# 9_STM32F407_Controller.net
KiCad netlist of a schematic drawn in Altium Designer
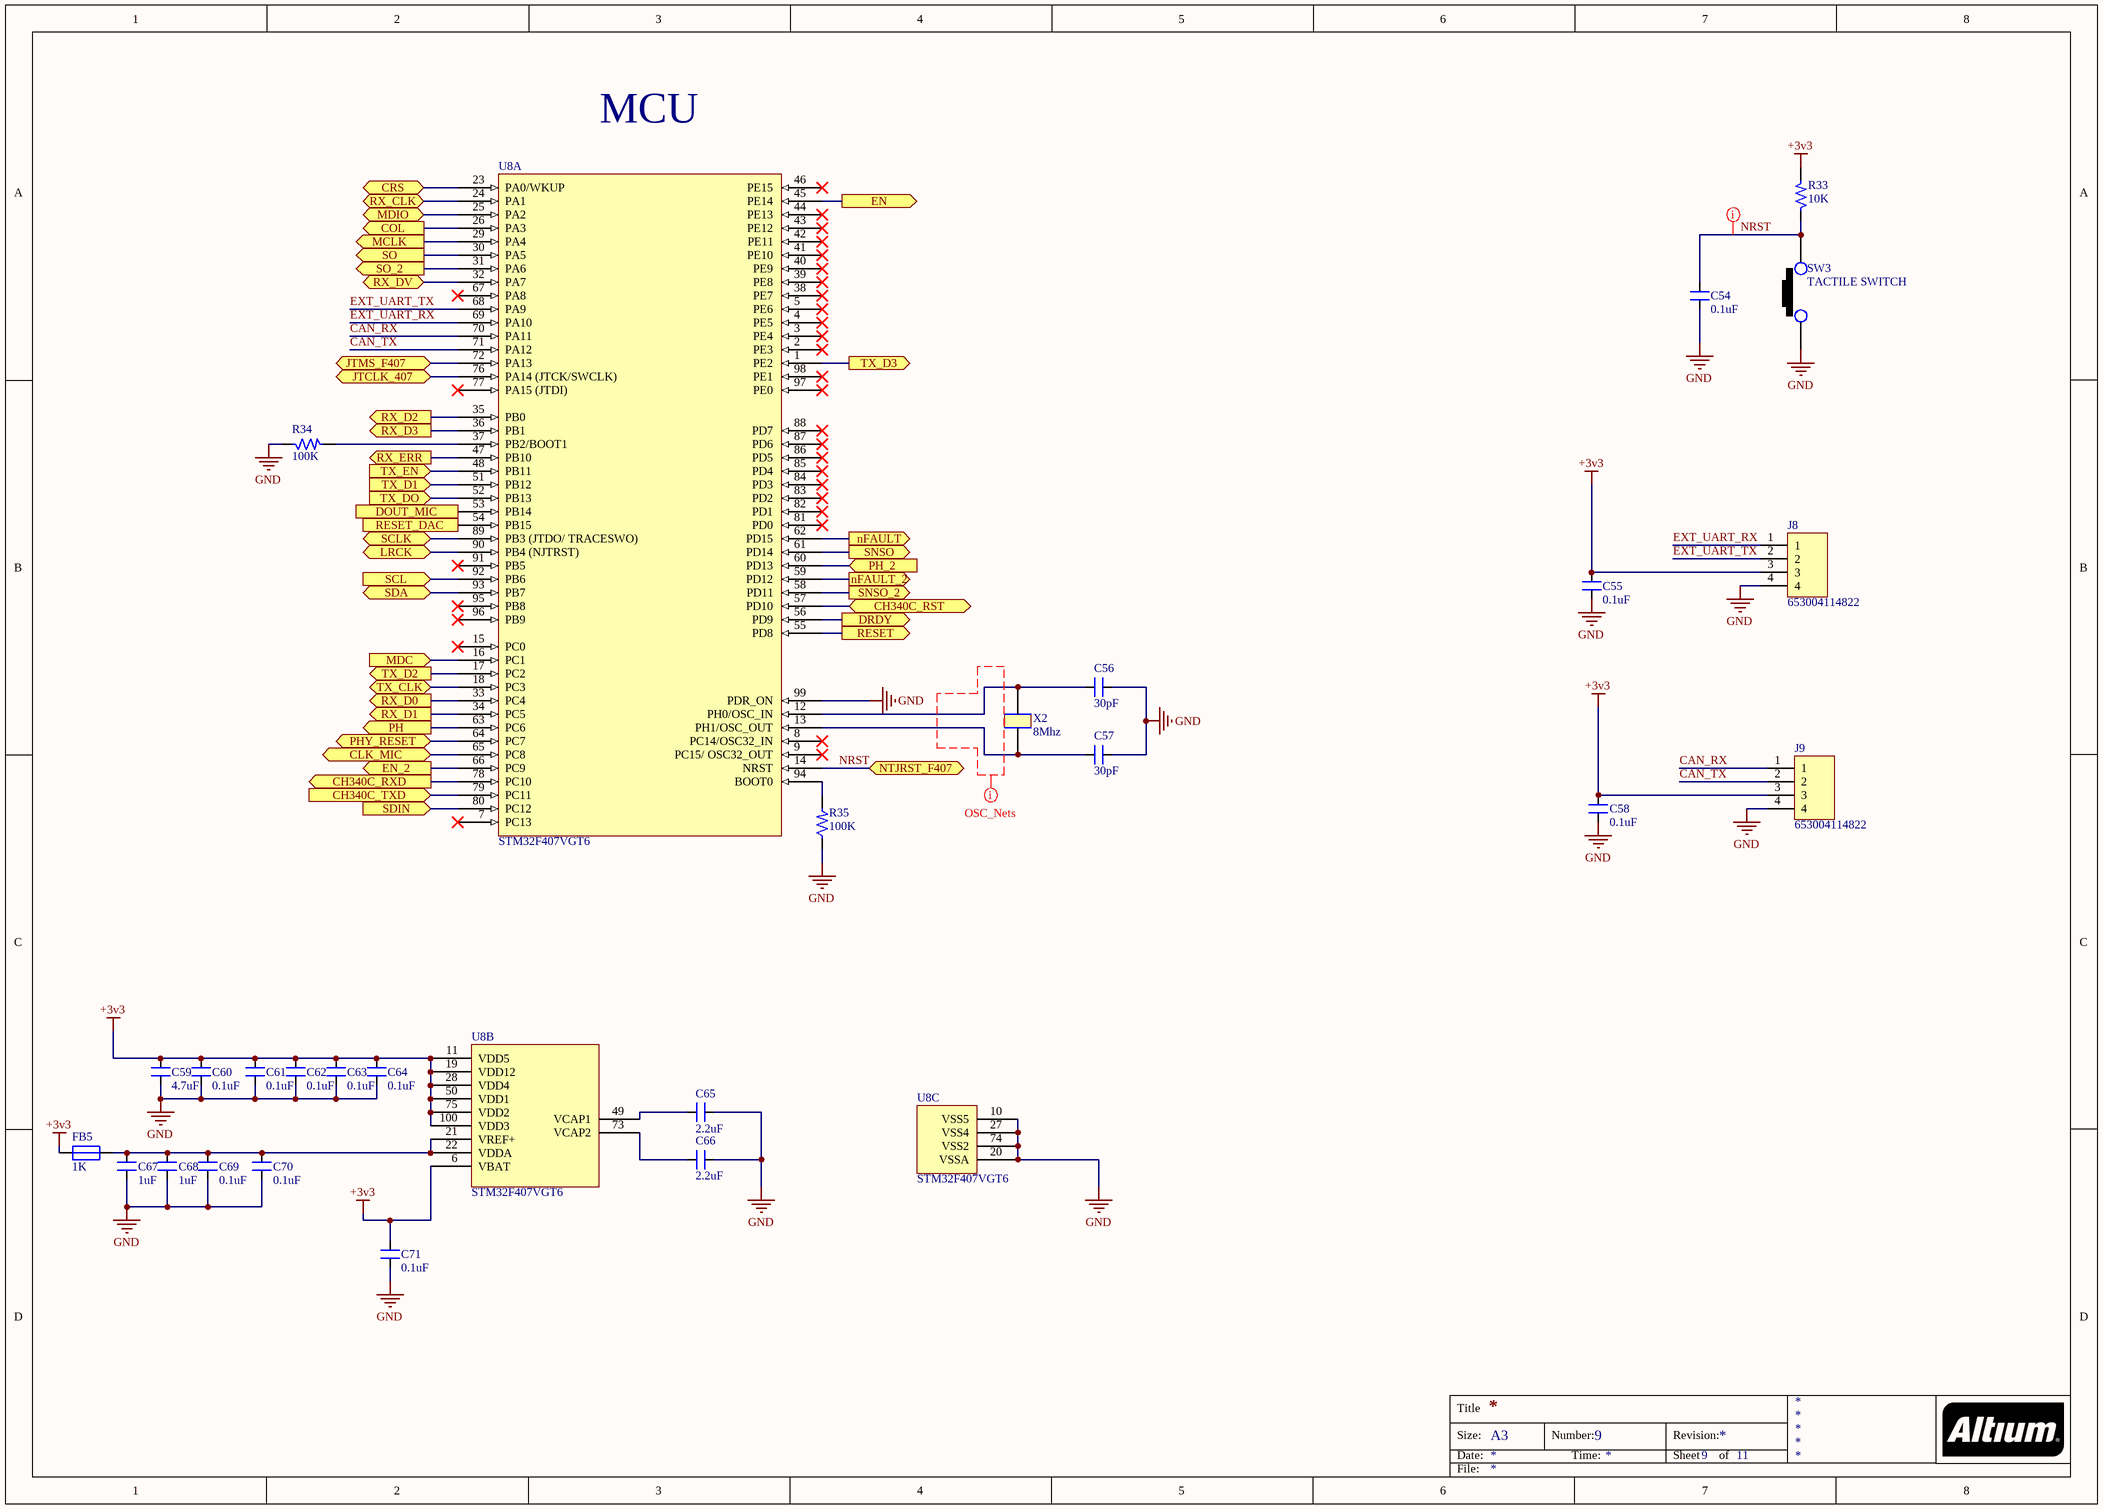
[diagram p0: [9]STM32F407_Controller.SchDoc]

(export (version "E")
  (design (tool "Eeschema 10.0.6"))
  (components
    (comp (ref "C54")
      (value "0.1uF")
      (footprint "CAP_0805")
      (description "0.1µF ±5% 50V Ceramic Capacitor X7R 0805 (2012 Metric)")
      (fields
        (field (name "MANUFACTURER") "AVX Corporation")
        (field (name "MANUFACTURER PART NUMBER") "08055C104JAT4A")
      )
      (libsource (lib "ESTEEMPCBLIB") (part "CAP_0.1uF-50V-5%-0805"))
    )
    (comp (ref "C55")
      (value "0.1uF")
      (footprint "CAP_0805")
      (description "0.1µF ±5% 50V Ceramic Capacitor X7R 0805 (2012 Metric)")
      (fields
        (field (name "MANUFACTURER") "AVX Corporation")
        (field (name "MANUFACTURER PART NUMBER") "08055C104JAT4A")
      )
      (libsource (lib "ESTEEMPCBLIB") (part "CAP_0.1uF-50V-5%-0805"))
    )
    (comp (ref "C56")
      (value "30pF")
      (footprint "CAP_0805")
      (description "±10% 50V Ceramic Capacitor C0G, NP0 0805 (2012 Metric)")
      (fields
        (field (name "MANUFACTURER PART NUMBER") "C0805C300K5GAC7800")
        (field (name "MANUFACTURER") "KEMET")
      )
      (libsource (lib "ESTEEMPCBLIB") (part "CAP_30pF-50V-10%-0805"))
    )
    (comp (ref "C57")
      (value "30pF")
      (footprint "CAP_0805")
      (description "±10% 50V Ceramic Capacitor C0G, NP0 0805 (2012 Metric)")
      (fields
        (field (name "MANUFACTURER PART NUMBER") "C0805C300K5GAC7800")
        (field (name "MANUFACTURER") "KEMET")
      )
      (libsource (lib "ESTEEMPCBLIB") (part "CAP_30pF-50V-10%-0805"))
    )
    (comp (ref "C58")
      (value "0.1uF")
      (footprint "CAP_0805")
      (description "0.1µF ±5% 50V Ceramic Capacitor X7R 0805 (2012 Metric)")
      (fields
        (field (name "MANUFACTURER") "AVX Corporation")
        (field (name "MANUFACTURER PART NUMBER") "08055C104JAT4A")
      )
      (libsource (lib "ESTEEMPCBLIB") (part "CAP_0.1uF-50V-5%-0805"))
    )
    (comp (ref "C59")
      (value "4.7uF")
      (footprint "CAP_0805")
      (description "1µF ±5% 50V Ceramic Capacitor X7R 0805 (2012 Metric)")
      (fields
        (field (name "MANUFACTURER") "Samsung")
        (field (name "MANUFACTURER PART NUMBER") "CC0805JKX7R9BB105")
      )
      (libsource (lib "ESTEEMPCBLIB") (part "CAP_1uF-50V-5%-0805"))
    )
    (comp (ref "C60")
      (value "0.1uF")
      (footprint "CAP_0805")
      (description "0.1µF ±5% 50V Ceramic Capacitor X7R 0805 (2012 Metric)")
      (fields
        (field (name "MANUFACTURER") "AVX Corporation")
        (field (name "MANUFACTURER PART NUMBER") "08055C104JAT4A")
      )
      (libsource (lib "ESTEEMPCBLIB") (part "CAP_0.1uF-50V-5%-0805"))
    )
    (comp (ref "C61")
      (value "0.1uF")
      (footprint "CAP_0805")
      (description "0.1µF ±5% 50V Ceramic Capacitor X7R 0805 (2012 Metric)")
      (fields
        (field (name "MANUFACTURER") "AVX Corporation")
        (field (name "MANUFACTURER PART NUMBER") "08055C104JAT4A")
      )
      (libsource (lib "ESTEEMPCBLIB") (part "CAP_0.1uF-50V-5%-0805"))
    )
    (comp (ref "C62")
      (value "0.1uF")
      (footprint "CAP_0805")
      (description "0.1µF ±5% 50V Ceramic Capacitor X7R 0805 (2012 Metric)")
      (fields
        (field (name "MANUFACTURER") "AVX Corporation")
        (field (name "MANUFACTURER PART NUMBER") "08055C104JAT4A")
      )
      (libsource (lib "ESTEEMPCBLIB") (part "CAP_0.1uF-50V-5%-0805"))
    )
    (comp (ref "C63")
      (value "0.1uF")
      (footprint "CAP_0805")
      (description "0.1µF ±5% 50V Ceramic Capacitor X7R 0805 (2012 Metric)")
      (fields
        (field (name "MANUFACTURER") "AVX Corporation")
        (field (name "MANUFACTURER PART NUMBER") "08055C104JAT4A")
      )
      (libsource (lib "ESTEEMPCBLIB") (part "CAP_0.1uF-50V-5%-0805"))
    )
    (comp (ref "C64")
      (value "0.1uF")
      (footprint "CAP_0805")
      (description "0.1µF ±5% 50V Ceramic Capacitor X7R 0805 (2012 Metric)")
      (fields
        (field (name "MANUFACTURER") "AVX Corporation")
        (field (name "MANUFACTURER PART NUMBER") "08055C104JAT4A")
      )
      (libsource (lib "ESTEEMPCBLIB") (part "CAP_0.1uF-50V-5%-0805"))
    )
    (comp (ref "C65")
      (value "2.2uF")
      (footprint "CAP_0805")
      (description "2.2µF ±10% 25V Ceramic Capacitor X7R 0805 (2012 Metric)")
      (fields
        (field (name "MANUFACTURER") "KEMET")
        (field (name "MANUFACTURER PART NUMBER") "CL21B225KAFNFNE")
      )
      (libsource (lib "ESTEEMPCBLIB") (part "CAP_2.2uF-25V-10%-0805"))
    )
    (comp (ref "C66")
      (value "2.2uF")
      (footprint "CAP_0805")
      (description "2.2µF ±10% 25V Ceramic Capacitor X7R 0805 (2012 Metric)")
      (fields
        (field (name "MANUFACTURER") "KEMET")
        (field (name "MANUFACTURER PART NUMBER") "CL21B225KAFNFNE")
      )
      (libsource (lib "ESTEEMPCBLIB") (part "CAP_2.2uF-25V-10%-0805"))
    )
    (comp (ref "C67")
      (value "1uF")
      (footprint "CAP_0805")
      (description "1µF ±5% 50V Ceramic Capacitor X7R 0805 (2012 Metric)")
      (fields
        (field (name "MANUFACTURER") "Samsung")
        (field (name "MANUFACTURER PART NUMBER") "CC0805JKX7R9BB105")
      )
      (libsource (lib "ESTEEMPCBLIB") (part "CAP_1uF-50V-5%-0805"))
    )
    (comp (ref "C68")
      (value "1uF")
      (footprint "CAP_0805")
      (description "1µF ±5% 50V Ceramic Capacitor X7R 0805 (2012 Metric)")
      (fields
        (field (name "MANUFACTURER") "Samsung")
        (field (name "MANUFACTURER PART NUMBER") "CC0805JKX7R9BB105")
      )
      (libsource (lib "ESTEEMPCBLIB") (part "CAP_1uF-50V-5%-0805"))
    )
    (comp (ref "C69")
      (value "0.1uF")
      (footprint "CAP_0805")
      (description "0.1µF ±5% 50V Ceramic Capacitor X7R 0805 (2012 Metric)")
      (fields
        (field (name "MANUFACTURER") "AVX Corporation")
        (field (name "MANUFACTURER PART NUMBER") "08055C104JAT4A")
      )
      (libsource (lib "ESTEEMPCBLIB") (part "CAP_0.1uF-50V-5%-0805"))
    )
    (comp (ref "C70")
      (value "0.1uF")
      (footprint "CAP_0805")
      (description "0.1µF ±5% 50V Ceramic Capacitor X7R 0805 (2012 Metric)")
      (fields
        (field (name "MANUFACTURER") "AVX Corporation")
        (field (name "MANUFACTURER PART NUMBER") "08055C104JAT4A")
      )
      (libsource (lib "ESTEEMPCBLIB") (part "CAP_0.1uF-50V-5%-0805"))
    )
    (comp (ref "C71")
      (value "0.1uF")
      (footprint "CAP_0805")
      (description "0.1µF ±5% 50V Ceramic Capacitor X7R 0805 (2012 Metric)")
      (fields
        (field (name "MANUFACTURER") "AVX Corporation")
        (field (name "MANUFACTURER PART NUMBER") "08055C104JAT4A")
      )
      (libsource (lib "ESTEEMPCBLIB") (part "CAP_0.1uF-50V-5%-0805"))
    )
    (comp (ref "FB5")
      (value "1K")
      (footprint "IND_0805")
      (description "1 kOhms @ 100MHz 1 Power Line Ferrite Bead 0805 (2012 Metric) 1.6A")
      (fields
        (field (name "MANUFACTURER") "Laird")
        (field (name "MANUFACTURER PART NUMBER") "BLM21SP102SH1D")
      )
      (libsource (lib "ESTEEMPCBLIB") (part "FB_1K-100MHZ-1.6A-0805"))
    )
    (comp (ref "J8")
      (value "653004114822")
      (footprint "CON4_50_653004114822_TH_ST")
      (description "4 Pins, 1 Row 1.25mm Pitch, straight Connector, male")
      (fields (field (name "MANUFACTURER") "JST") (field (name "MATING PART NUMBER") "653004113322"))
      (libsource (lib "ESTEEMPCBLIB") (part "CON-PLG_4X1-50-ST-TH"))
    )
    (comp (ref "J9")
      (value "653004114822")
      (footprint "CON4_50_653004114822_TH_ST")
      (description "4 Pins, 1 Row 1.25mm Pitch, straight Connector, male")
      (fields (field (name "MANUFACTURER") "JST") (field (name "MATING PART NUMBER") "653004113322"))
      (libsource (lib "ESTEEMPCBLIB") (part "CON-PLG_4X1-50-ST-TH"))
    )
    (comp (ref "R33")
      (value "10K")
      (footprint "RES_0805")
      (description "10 kOhms ±1% 0.125W, 1/8W Chip Resistor 0805 (2012 Metric) Automotive AEC-Q200 Thick Film")
      (fields (field (name "MANUFACTURER") "CTS") (field (name "MANUFACTURER PART NUMBER") "WR08X1002FTL"))
      (libsource (lib "ESTEEMPCBLIB") (part "RES_10K-0.125W-1%-0805"))
    )
    (comp (ref "R34")
      (value "100K")
      (footprint "RES_0805")
      (description "100 kOhms ±1% 0.125W, 1/8W Chip Resistor 0805 (2012 Metric) Automotive AEC-Q200 Thick Film")
      (fields (field (name "MANUFACTURER") "Walsin") (field (name "MANUFACTURER PART NUMBER") "WR08X1003FTL"))
      (libsource (lib "ESTEEMPCBLIB") (part "RES_100K-0.125W-1%-0805"))
    )
    (comp (ref "R35")
      (value "100K")
      (footprint "RES_0805")
      (description "100 kOhms ±1% 0.125W, 1/8W Chip Resistor 0805 (2012 Metric) Automotive AEC-Q200 Thick Film")
      (fields (field (name "MANUFACTURER") "Walsin") (field (name "MANUFACTURER PART NUMBER") "WR08X1003FTL"))
      (libsource (lib "ESTEEMPCBLIB") (part "RES_100K-0.125W-1%-0805"))
    )
    (comp (ref "SW3")
      (value "TACTILE SWITCH")
      (footprint "SW_342_SMD")
      (description "Tactile Switch SPST-NO Top Actuated Surface Mount")
      (fields
        (field (name "MANUFACTURER") "ITT C&K")
        (field (name "MANUFACTURER PART NUMBER") "RS-282G05A3-SMRT")
      )
      (libsource (lib "ESTEEMPCBLIB") (part "SW1_RS-282G05A3-SMRT-SMD"))
    )
    (comp (ref "U8")
      (value "STM32F407VGT6")
      (footprint "QFN100_19.6_669_58X10_SMD")
      (description "ARM® Cortex®-M4 STM32F4 Microcontroller IC 32-Bit 168MHz 1MB (1M x 8) FLASH 100-LQFP (14x14)")
      (fields (field (name "MANUFACTURER") "STMicroelectronics"))
      (libsource (lib "ESTEEMPCBLIB") (part "IC_STM32F407VGT6"))
    )
    (comp (ref "X2")
      (value "8Mhz")
      (footprint "XTAL_314_240X47_SMD")
      (description "8MHz ±30ppm Crystal 32pF 60 Ohms HC-49/US")
      (fields
        (field (name "MANUFACTURER") "Fox Electronics")
        (field (name "MANUFACTURER PART NUMBER") "ECS-80-32-5PX-TR")
      )
      (libsource (lib "ESTEEMPCBLIB") (part "XTAL_8MHZ-ECS-80-32-5PX-SMD"))
    )
  )
  (nets
    (net (code "1") (name "+3v3") (class "Default")
      (node (ref "C55") (pin "2") (pinfunction "2_2") (pintype "passive"))
      (node (ref "C58") (pin "2") (pinfunction "2_2") (pintype "passive"))
      (node (ref "C59") (pin "2") (pinfunction "2_2") (pintype "passive"))
      (node (ref "C60") (pin "2") (pinfunction "2_2") (pintype "passive"))
      (node (ref "C61") (pin "2") (pinfunction "2_2") (pintype "passive"))
      (node (ref "C62") (pin "2") (pinfunction "2_2") (pintype "passive"))
      (node (ref "C63") (pin "2") (pinfunction "2_2") (pintype "passive"))
      (node (ref "C64") (pin "2") (pinfunction "2_2") (pintype "passive"))
      (node (ref "C71") (pin "2") (pinfunction "2_2") (pintype "passive"))
      (node (ref "FB5") (pin "1") (pinfunction "1_1") (pintype "passive"))
      (node (ref "J8") (pin "3") (pinfunction "3_3") (pintype "passive"))
      (node (ref "J9") (pin "3") (pinfunction "3_3") (pintype "passive"))
      (node (ref "R33") (pin "2") (pinfunction "2_2") (pintype "passive"))
      (node (ref "U8") (pin "100") (pinfunction "VDD3_100") (pintype "passive"))
      (node (ref "U8") (pin "11") (pinfunction "VDD5_11") (pintype "passive"))
      (node (ref "U8") (pin "19") (pinfunction "VDD12_19") (pintype "passive"))
      (node (ref "U8") (pin "28") (pinfunction "VDD4_28") (pintype "passive"))
      (node (ref "U8") (pin "50") (pinfunction "VDD1_50") (pintype "passive"))
      (node (ref "U8") (pin "6") (pinfunction "VBAT_6") (pintype "passive"))
      (node (ref "U8") (pin "75") (pinfunction "VDD2_75") (pintype "passive"))
    )
    (net (code "2") (name "/CAN_RX") (class "Default")
      (node (ref "J9") (pin "1") (pinfunction "1_1") (pintype "passive"))
      (node (ref "U8") (pin "70") (pinfunction "PA11_70") (pintype "input"))
    )
    (net (code "3") (name "/CAN_TX") (class "Default")
      (node (ref "J9") (pin "2") (pinfunction "2_2") (pintype "passive"))
      (node (ref "U8") (pin "71") (pinfunction "PA12_71") (pintype "input"))
    )
    (net (code "4") (name "/CH340C_RST") (class "Default")
      (node (ref "U8") (pin "57") (pinfunction "PD10_57") (pintype "input"))
    )
    (net (code "5") (name "/CH340C_RXD") (class "Default")
      (node (ref "U8") (pin "78") (pinfunction "PC10_78") (pintype "input"))
    )
    (net (code "6") (name "/CH340C_TXD") (class "Default")
      (node (ref "U8") (pin "79") (pinfunction "PC11_79") (pintype "input"))
    )
    (net (code "7") (name "/CLK_MIC") (class "Default")
      (node (ref "U8") (pin "65") (pinfunction "PC8_65") (pintype "input"))
    )
    (net (code "8") (name "/COL") (class "Default")
      (node (ref "U8") (pin "26") (pinfunction "PA3_26") (pintype "input"))
    )
    (net (code "9") (name "/CRS") (class "Default")
      (node (ref "U8") (pin "23") (pinfunction "PA0/WKUP_23") (pintype "input"))
    )
    (net (code "10") (name "/DOUT_MIC") (class "Default")
      (node (ref "U8") (pin "53") (pinfunction "PB14_53") (pintype "input"))
    )
    (net (code "11") (name "/DRDY") (class "Default")
      (node (ref "U8") (pin "56") (pinfunction "PD9_56") (pintype "input"))
    )
    (net (code "12") (name "/EN") (class "Default")
      (node (ref "U8") (pin "45") (pinfunction "PE14_45") (pintype "input"))
    )
    (net (code "13") (name "/EN_2") (class "Default")
      (node (ref "U8") (pin "66") (pinfunction "PC9_66") (pintype "input"))
    )
    (net (code "14") (name "/EXT_UART_RX") (class "Default")
      (node (ref "J8") (pin "1") (pinfunction "1_1") (pintype "passive"))
      (node (ref "U8") (pin "69") (pinfunction "PA10_69") (pintype "input"))
    )
    (net (code "15") (name "/EXT_UART_TX") (class "Default")
      (node (ref "J8") (pin "2") (pinfunction "2_2") (pintype "passive"))
      (node (ref "U8") (pin "68") (pinfunction "PA9_68") (pintype "input"))
    )
    (net (code "16") (name "/JTCLK_407") (class "Default")
      (node (ref "U8") (pin "76") (pinfunction "PA14_(JTCK/SWCLK)_76") (pintype "input"))
    )
    (net (code "17") (name "/JTMS_F407") (class "Default")
      (node (ref "U8") (pin "72") (pinfunction "PA13_72") (pintype "input"))
    )
    (net (code "18") (name "/LRCK") (class "Default")
      (node (ref "U8") (pin "90") (pinfunction "PB4_(NJTRST)_90") (pintype "input"))
    )
    (net (code "19") (name "/MCLK") (class "Default")
      (node (ref "U8") (pin "29") (pinfunction "PA4_29") (pintype "input"))
    )
    (net (code "20") (name "/MDC") (class "Default")
      (node (ref "U8") (pin "16") (pinfunction "PC1_16") (pintype "input"))
    )
    (net (code "21") (name "/MDIO") (class "Default")
      (node (ref "U8") (pin "25") (pinfunction "PA2_25") (pintype "input"))
    )
    (net (code "22") (name "/NRST") (class "Default")
      (node (ref "C54") (pin "2") (pinfunction "2_2") (pintype "passive"))
      (node (ref "R33") (pin "1") (pinfunction "1_1") (pintype "passive"))
      (node (ref "SW3") (pin "2") (pinfunction "2_2") (pintype "passive"))
      (node (ref "U8") (pin "14") (pinfunction "NRST_14") (pintype "input"))
    )
    (net (code "23") (name "/PH") (class "Default")
      (node (ref "U8") (pin "63") (pinfunction "PC6_63") (pintype "input"))
    )
    (net (code "24") (name "/PHY_RESET") (class "Default")
      (node (ref "U8") (pin "64") (pinfunction "PC7_64") (pintype "input"))
    )
    (net (code "25") (name "/PH_2") (class "Default")
      (node (ref "U8") (pin "60") (pinfunction "PD13_60") (pintype "input"))
    )
    (net (code "26") (name "/RESET") (class "Default")
      (node (ref "U8") (pin "55") (pinfunction "PD8_55") (pintype "input"))
    )
    (net (code "27") (name "/RESET_DAC") (class "Default")
      (node (ref "U8") (pin "54") (pinfunction "PB15_54") (pintype "input"))
    )
    (net (code "28") (name "/RX_CLK") (class "Default")
      (node (ref "U8") (pin "24") (pinfunction "PA1_24") (pintype "input"))
    )
    (net (code "29") (name "/RX_D0") (class "Default")
      (node (ref "U8") (pin "33") (pinfunction "PC4_33") (pintype "input"))
    )
    (net (code "30") (name "/RX_D1") (class "Default")
      (node (ref "U8") (pin "34") (pinfunction "PC5_34") (pintype "input"))
    )
    (net (code "31") (name "/RX_D2") (class "Default")
      (node (ref "U8") (pin "35") (pinfunction "PB0_35") (pintype "input"))
    )
    (net (code "32") (name "/RX_D3") (class "Default")
      (node (ref "U8") (pin "36") (pinfunction "PB1_36") (pintype "input"))
    )
    (net (code "33") (name "/RX_DV") (class "Default")
      (node (ref "U8") (pin "32") (pinfunction "PA7_32") (pintype "input"))
    )
    (net (code "34") (name "/RX_ERR") (class "Default")
      (node (ref "U8") (pin "47") (pinfunction "PB10_47") (pintype "input"))
    )
    (net (code "35") (name "/SCL") (class "Default")
      (node (ref "U8") (pin "92") (pinfunction "PB6_92") (pintype "input"))
    )
    (net (code "36") (name "/SCLK") (class "Default")
      (node (ref "U8") (pin "89") (pinfunction "PB3_(JTDO/_TRACESWO)_89") (pintype "input"))
    )
    (net (code "37") (name "/SDA") (class "Default")
      (node (ref "U8") (pin "93") (pinfunction "PB7_93") (pintype "input"))
    )
    (net (code "38") (name "/SDIN") (class "Default")
      (node (ref "U8") (pin "80") (pinfunction "PC12_80") (pintype "input"))
    )
    (net (code "39") (name "/SNSO") (class "Default")
      (node (ref "U8") (pin "61") (pinfunction "PD14_61") (pintype "input"))
    )
    (net (code "40") (name "/SNSO_2") (class "Default")
      (node (ref "U8") (pin "58") (pinfunction "PD11_58") (pintype "input"))
    )
    (net (code "41") (name "/SO") (class "Default")
      (node (ref "U8") (pin "30") (pinfunction "PA5_30") (pintype "input"))
    )
    (net (code "42") (name "/SO_2") (class "Default")
      (node (ref "U8") (pin "31") (pinfunction "PA6_31") (pintype "input"))
    )
    (net (code "43") (name "/TX_CLK") (class "Default")
      (node (ref "U8") (pin "18") (pinfunction "PC3_18") (pintype "input"))
    )
    (net (code "44") (name "/TX_D1") (class "Default")
      (node (ref "U8") (pin "51") (pinfunction "PB12_51") (pintype "input"))
    )
    (net (code "45") (name "/TX_D2") (class "Default")
      (node (ref "U8") (pin "17") (pinfunction "PC2_17") (pintype "input"))
    )
    (net (code "46") (name "/TX_D3") (class "Default")
      (node (ref "U8") (pin "1") (pinfunction "PE2_1") (pintype "input"))
    )
    (net (code "47") (name "/TX_DO") (class "Default")
      (node (ref "U8") (pin "52") (pinfunction "PB13_52") (pintype "input"))
    )
    (net (code "48") (name "/TX_EN") (class "Default")
      (node (ref "U8") (pin "48") (pinfunction "PB11_48") (pintype "input"))
    )
    (net (code "49") (name "/nFAULT") (class "Default")
      (node (ref "U8") (pin "62") (pinfunction "PD15_62") (pintype "input"))
    )
    (net (code "50") (name "/nFAULT_2") (class "Default")
      (node (ref "U8") (pin "59") (pinfunction "PD12_59") (pintype "input"))
    )
    (net (code "51") (name "GND") (class "Default")
      (node (ref "C54") (pin "1") (pinfunction "1_1") (pintype "passive"))
      (node (ref "C55") (pin "1") (pinfunction "1_1") (pintype "passive"))
      (node (ref "C56") (pin "2") (pinfunction "2_2") (pintype "passive"))
      (node (ref "C57") (pin "2") (pinfunction "2_2") (pintype "passive"))
      (node (ref "C58") (pin "1") (pinfunction "1_1") (pintype "passive"))
      (node (ref "C59") (pin "1") (pinfunction "1_1") (pintype "passive"))
      (node (ref "C60") (pin "1") (pinfunction "1_1") (pintype "passive"))
      (node (ref "C61") (pin "1") (pinfunction "1_1") (pintype "passive"))
      (node (ref "C62") (pin "1") (pinfunction "1_1") (pintype "passive"))
      (node (ref "C63") (pin "1") (pinfunction "1_1") (pintype "passive"))
      (node (ref "C64") (pin "1") (pinfunction "1_1") (pintype "passive"))
      (node (ref "C65") (pin "2") (pinfunction "2_2") (pintype "passive"))
      (node (ref "C66") (pin "2") (pinfunction "2_2") (pintype "passive"))
      (node (ref "C67") (pin "1") (pinfunction "1_1") (pintype "passive"))
      (node (ref "C68") (pin "1") (pinfunction "1_1") (pintype "passive"))
      (node (ref "C69") (pin "1") (pinfunction "1_1") (pintype "passive"))
      (node (ref "C70") (pin "1") (pinfunction "1_1") (pintype "passive"))
      (node (ref "C71") (pin "1") (pinfunction "1_1") (pintype "passive"))
      (node (ref "J8") (pin "4") (pinfunction "4_4") (pintype "passive"))
      (node (ref "J9") (pin "4") (pinfunction "4_4") (pintype "passive"))
      (node (ref "R34") (pin "1") (pinfunction "1_1") (pintype "passive"))
      (node (ref "R35") (pin "1") (pinfunction "1_1") (pintype "passive"))
      (node (ref "SW3") (pin "1") (pinfunction "1_1") (pintype "passive"))
      (node (ref "U8") (pin "10") (pinfunction "VSS5_10") (pintype "passive"))
      (node (ref "U8") (pin "20") (pinfunction "VSSA_20") (pintype "passive"))
      (node (ref "U8") (pin "27") (pinfunction "VSS4_27") (pintype "passive"))
      (node (ref "U8") (pin "74") (pinfunction "VSS2_74") (pintype "passive"))
      (node (ref "U8") (pin "99") (pinfunction "PDR_ON_99") (pintype "input"))
    )
    (net (code "52") (name "Net-(U8A-BOOT0)") (class "Default")
      (node (ref "R35") (pin "2") (pinfunction "2_2") (pintype "passive"))
      (node (ref "U8") (pin "94") (pinfunction "BOOT0_94") (pintype "input"))
    )
    (net (code "53") (name "Net-(U8A-PB2{slash}BOOT1)") (class "Default")
      (node (ref "R34") (pin "2") (pinfunction "2_2") (pintype "passive"))
      (node (ref "U8") (pin "37") (pinfunction "PB2/BOOT1_37") (pintype "input"))
    )
    (net (code "54") (name "Net-(U8A-PH0{slash}OSC_IN)") (class "Default")
      (node (ref "C56") (pin "1") (pinfunction "1_1") (pintype "passive"))
      (node (ref "U8") (pin "12") (pinfunction "PH0/OSC_IN_12") (pintype "input"))
      (node (ref "X2") (pin "2") (pinfunction "2_2") (pintype "passive"))
    )
    (net (code "55") (name "Net-(U8A-PH1{slash}OSC_OUT)") (class "Default")
      (node (ref "C57") (pin "1") (pinfunction "1_1") (pintype "passive"))
      (node (ref "U8") (pin "13") (pinfunction "PH1/OSC_OUT_13") (pintype "input"))
      (node (ref "X2") (pin "1") (pinfunction "1_1") (pintype "passive"))
    )
    (net (code "56") (name "Net-(U8B-VCAP1)") (class "Default")
      (node (ref "C65") (pin "1") (pinfunction "1_1") (pintype "passive"))
      (node (ref "U8") (pin "49") (pinfunction "VCAP1_49") (pintype "passive"))
    )
    (net (code "57") (name "Net-(U8B-VCAP2)") (class "Default")
      (node (ref "C66") (pin "1") (pinfunction "1_1") (pintype "passive"))
      (node (ref "U8") (pin "73") (pinfunction "VCAP2_73") (pintype "passive"))
    )
    (net (code "58") (name "Net-(U8B-VDDA)") (class "Default")
      (node (ref "C67") (pin "2") (pinfunction "2_2") (pintype "passive"))
      (node (ref "C68") (pin "2") (pinfunction "2_2") (pintype "passive"))
      (node (ref "C69") (pin "2") (pinfunction "2_2") (pintype "passive"))
      (node (ref "C70") (pin "2") (pinfunction "2_2") (pintype "passive"))
      (node (ref "FB5") (pin "2") (pinfunction "2_2") (pintype "passive"))
      (node (ref "U8") (pin "21") (pinfunction "VREF+_21") (pintype "passive"))
      (node (ref "U8") (pin "22") (pinfunction "VDDA_22") (pintype "passive"))
    )
    (net (code "59") (name "unconnected-(U8A-PA8-Pad67)") (class "Default")
      (node (ref "U8") (pin "67") (pinfunction "PA8_67") (pintype "input+no_connect"))
    )
    (net (code "60") (name "unconnected-(U8A-PA15_(JTDI)-Pad77)") (class "Default")
      (node (ref "U8") (pin "77") (pinfunction "PA15_(JTDI)_77") (pintype "input+no_connect"))
    )
    (net (code "61") (name "unconnected-(U8A-PB5-Pad91)") (class "Default")
      (node (ref "U8") (pin "91") (pinfunction "PB5_91") (pintype "input+no_connect"))
    )
    (net (code "62") (name "unconnected-(U8A-PB8-Pad95)") (class "Default")
      (node (ref "U8") (pin "95") (pinfunction "PB8_95") (pintype "input+no_connect"))
    )
    (net (code "63") (name "unconnected-(U8A-PB9-Pad96)") (class "Default")
      (node (ref "U8") (pin "96") (pinfunction "PB9_96") (pintype "input+no_connect"))
    )
    (net (code "64") (name "unconnected-(U8A-PC0-Pad15)") (class "Default")
      (node (ref "U8") (pin "15") (pinfunction "PC0_15") (pintype "input+no_connect"))
    )
    (net (code "65") (name "unconnected-(U8A-PC13-Pad7)") (class "Default")
      (node (ref "U8") (pin "7") (pinfunction "PC13_7") (pintype "input+no_connect"))
    )
    (net (code "66") (name "unconnected-(U8A-PC14{slash}OSC32_IN-Pad8)") (class "Default")
      (node (ref "U8") (pin "8") (pinfunction "PC14/OSC32_IN_8") (pintype "input+no_connect"))
    )
    (net (code "67") (name "unconnected-(U8A-PC15{slash}_OSC32_OUT-Pad9)") (class "Default")
      (node (ref "U8") (pin "9") (pinfunction "PC15/_OSC32_OUT_9") (pintype "input+no_connect"))
    )
    (net (code "68") (name "unconnected-(U8A-PD0-Pad81)") (class "Default")
      (node (ref "U8") (pin "81") (pinfunction "PD0_81") (pintype "input+no_connect"))
    )
    (net (code "69") (name "unconnected-(U8A-PD1-Pad82)") (class "Default")
      (node (ref "U8") (pin "82") (pinfunction "PD1_82") (pintype "input+no_connect"))
    )
    (net (code "70") (name "unconnected-(U8A-PD2-Pad83)") (class "Default")
      (node (ref "U8") (pin "83") (pinfunction "PD2_83") (pintype "input+no_connect"))
    )
    (net (code "71") (name "unconnected-(U8A-PD3-Pad84)") (class "Default")
      (node (ref "U8") (pin "84") (pinfunction "PD3_84") (pintype "input+no_connect"))
    )
    (net (code "72") (name "unconnected-(U8A-PD4-Pad85)") (class "Default")
      (node (ref "U8") (pin "85") (pinfunction "PD4_85") (pintype "input+no_connect"))
    )
    (net (code "73") (name "unconnected-(U8A-PD5-Pad86)") (class "Default")
      (node (ref "U8") (pin "86") (pinfunction "PD5_86") (pintype "input+no_connect"))
    )
    (net (code "74") (name "unconnected-(U8A-PD6-Pad87)") (class "Default")
      (node (ref "U8") (pin "87") (pinfunction "PD6_87") (pintype "input+no_connect"))
    )
    (net (code "75") (name "unconnected-(U8A-PD7-Pad88)") (class "Default")
      (node (ref "U8") (pin "88") (pinfunction "PD7_88") (pintype "input+no_connect"))
    )
    (net (code "76") (name "unconnected-(U8A-PE0-Pad97)") (class "Default")
      (node (ref "U8") (pin "97") (pinfunction "PE0_97") (pintype "input+no_connect"))
    )
    (net (code "77") (name "unconnected-(U8A-PE1-Pad98)") (class "Default")
      (node (ref "U8") (pin "98") (pinfunction "PE1_98") (pintype "input+no_connect"))
    )
    (net (code "78") (name "unconnected-(U8A-PE3-Pad2)") (class "Default")
      (node (ref "U8") (pin "2") (pinfunction "PE3_2") (pintype "input+no_connect"))
    )
    (net (code "79") (name "unconnected-(U8A-PE4-Pad3)") (class "Default")
      (node (ref "U8") (pin "3") (pinfunction "PE4_3") (pintype "input+no_connect"))
    )
    (net (code "80") (name "unconnected-(U8A-PE5-Pad4)") (class "Default")
      (node (ref "U8") (pin "4") (pinfunction "PE5_4") (pintype "input+no_connect"))
    )
    (net (code "81") (name "unconnected-(U8A-PE6-Pad5)") (class "Default")
      (node (ref "U8") (pin "5") (pinfunction "PE6_5") (pintype "input+no_connect"))
    )
    (net (code "82") (name "unconnected-(U8A-PE7-Pad38)") (class "Default")
      (node (ref "U8") (pin "38") (pinfunction "PE7_38") (pintype "input+no_connect"))
    )
    (net (code "83") (name "unconnected-(U8A-PE8-Pad39)") (class "Default")
      (node (ref "U8") (pin "39") (pinfunction "PE8_39") (pintype "input+no_connect"))
    )
    (net (code "84") (name "unconnected-(U8A-PE9-Pad40)") (class "Default")
      (node (ref "U8") (pin "40") (pinfunction "PE9_40") (pintype "input+no_connect"))
    )
    (net (code "85") (name "unconnected-(U8A-PE10-Pad41)") (class "Default")
      (node (ref "U8") (pin "41") (pinfunction "PE10_41") (pintype "input+no_connect"))
    )
    (net (code "86") (name "unconnected-(U8A-PE11-Pad42)") (class "Default")
      (node (ref "U8") (pin "42") (pinfunction "PE11_42") (pintype "input+no_connect"))
    )
    (net (code "87") (name "unconnected-(U8A-PE12-Pad43)") (class "Default")
      (node (ref "U8") (pin "43") (pinfunction "PE12_43") (pintype "input+no_connect"))
    )
    (net (code "88") (name "unconnected-(U8A-PE13-Pad44)") (class "Default")
      (node (ref "U8") (pin "44") (pinfunction "PE13_44") (pintype "input+no_connect"))
    )
    (net (code "89") (name "unconnected-(U8A-PE15-Pad46)") (class "Default")
      (node (ref "U8") (pin "46") (pinfunction "PE15_46") (pintype "input+no_connect"))
    )
  )
)
